# ODROID.net
KiCad netlist of a schematic drawn in Altium Designer
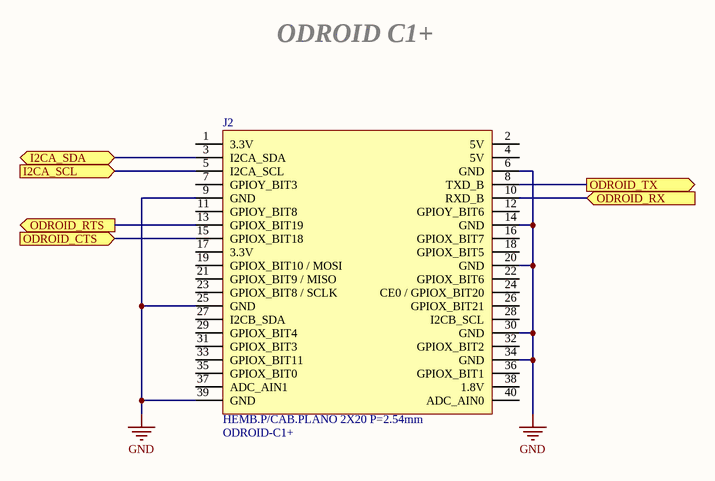
[diagram p0: ODROID.SchDoc]

(export (version "E")
  (design (tool "Eeschema 10.0.6"))
  (components
    (comp (ref "J2")
      (value "HEMB.P/CAB.PLANO 2X20 P=2.54mm")
      (footprint "ODROID_C1+_MOUNTUP")
      (description "Conector para odroid c1+")
      (fields (field (name "ALTIUM_UNNAMED_1") "ODROID-C1+"))
      (libsource (lib "HW_Dron_V2") (part "Odroid_C1+"))
    )
  )
  (nets
    (net (code "1") (name "/I2CA_SCL") (class "Default")
      (node (ref "J2") (pin "5") (pinfunction "I2CA_SCL_5") (pintype "passive"))
    )
    (net (code "2") (name "/I2CA_SDA") (class "Default")
      (node (ref "J2") (pin "3") (pinfunction "I2CA_SDA_3") (pintype "passive"))
    )
    (net (code "3") (name "/ODROID_CTS") (class "Default")
      (node (ref "J2") (pin "15") (pinfunction "GPIOX_BIT18_15") (pintype "passive"))
    )
    (net (code "4") (name "/ODROID_RTS") (class "Default")
      (node (ref "J2") (pin "13") (pinfunction "GPIOX_BIT19_13") (pintype "passive"))
    )
    (net (code "5") (name "/ODROID_RX") (class "Default")
      (node (ref "J2") (pin "10") (pinfunction "RXD_B_10") (pintype "passive"))
    )
    (net (code "6") (name "/ODROID_TX") (class "Default")
      (node (ref "J2") (pin "8") (pinfunction "TXD_B_8") (pintype "passive"))
    )
    (net (code "7") (name "GND") (class "Default")
      (node (ref "J2") (pin "14") (pinfunction "GND_14") (pintype "passive"))
      (node (ref "J2") (pin "20") (pinfunction "GND_20") (pintype "passive"))
      (node (ref "J2") (pin "25") (pinfunction "GND_25") (pintype "passive"))
      (node (ref "J2") (pin "30") (pinfunction "GND_30") (pintype "passive"))
      (node (ref "J2") (pin "34") (pinfunction "GND_34") (pintype "passive"))
      (node (ref "J2") (pin "39") (pinfunction "GND_39") (pintype "passive"))
      (node (ref "J2") (pin "6") (pinfunction "GND_6") (pintype "passive"))
      (node (ref "J2") (pin "9") (pinfunction "GND_9") (pintype "passive"))
    )
    (net (code "8") (name "unconnected-(J2-1.8V-Pad38)") (class "Default")
      (node (ref "J2") (pin "38") (pinfunction "1.8V_38") (pintype "passive"))
    )
    (net (code "9") (name "unconnected-(J2-3.3V-Pad1)") (class "Default")
      (node (ref "J2") (pin "1") (pinfunction "3.3V_1") (pintype "passive"))
    )
    (net (code "10") (name "unconnected-(J2-3.3V-Pad17)") (class "Default")
      (node (ref "J2") (pin "17") (pinfunction "3.3V_17") (pintype "passive"))
    )
    (net (code "11") (name "unconnected-(J2-5V-Pad2)") (class "Default")
      (node (ref "J2") (pin "2") (pinfunction "5V_2") (pintype "passive"))
    )
    (net (code "12") (name "unconnected-(J2-5V-Pad4)") (class "Default")
      (node (ref "J2") (pin "4") (pinfunction "5V_4") (pintype "passive"))
    )
    (net (code "13") (name "unconnected-(J2-ADC_AIN0-Pad40)") (class "Default")
      (node (ref "J2") (pin "40") (pinfunction "ADC_AIN0_40") (pintype "passive"))
    )
    (net (code "14") (name "unconnected-(J2-ADC_AIN1-Pad37)") (class "Default")
      (node (ref "J2") (pin "37") (pinfunction "ADC_AIN1_37") (pintype "passive"))
    )
    (net (code "15") (name "unconnected-(J2-CE0_{slash}_GPIOX_BIT20-Pad24)") (class "Default")
      (node (ref "J2") (pin "24") (pinfunction "CE0_/_GPIOX_BIT20_24") (pintype "passive"))
    )
    (net (code "16") (name "unconnected-(J2-GPIOX_BIT0-Pad35)") (class "Default")
      (node (ref "J2") (pin "35") (pinfunction "GPIOX_BIT0_35") (pintype "passive"))
    )
    (net (code "17") (name "unconnected-(J2-GPIOX_BIT1-Pad36)") (class "Default")
      (node (ref "J2") (pin "36") (pinfunction "GPIOX_BIT1_36") (pintype "passive"))
    )
    (net (code "18") (name "unconnected-(J2-GPIOX_BIT2-Pad32)") (class "Default")
      (node (ref "J2") (pin "32") (pinfunction "GPIOX_BIT2_32") (pintype "passive"))
    )
    (net (code "19") (name "unconnected-(J2-GPIOX_BIT3-Pad31)") (class "Default")
      (node (ref "J2") (pin "31") (pinfunction "GPIOX_BIT3_31") (pintype "passive"))
    )
    (net (code "20") (name "unconnected-(J2-GPIOX_BIT4-Pad29)") (class "Default")
      (node (ref "J2") (pin "29") (pinfunction "GPIOX_BIT4_29") (pintype "passive"))
    )
    (net (code "21") (name "unconnected-(J2-GPIOX_BIT5-Pad18)") (class "Default")
      (node (ref "J2") (pin "18") (pinfunction "GPIOX_BIT5_18") (pintype "passive"))
    )
    (net (code "22") (name "unconnected-(J2-GPIOX_BIT6-Pad22)") (class "Default")
      (node (ref "J2") (pin "22") (pinfunction "GPIOX_BIT6_22") (pintype "passive"))
    )
    (net (code "23") (name "unconnected-(J2-GPIOX_BIT7-Pad16)") (class "Default")
      (node (ref "J2") (pin "16") (pinfunction "GPIOX_BIT7_16") (pintype "passive"))
    )
    (net (code "24") (name "unconnected-(J2-GPIOX_BIT8_{slash}_SCLK-Pad23)") (class "Default")
      (node (ref "J2") (pin "23") (pinfunction "GPIOX_BIT8_/_SCLK_23") (pintype "passive"))
    )
    (net (code "25") (name "unconnected-(J2-GPIOX_BIT9_{slash}_MISO-Pad21)") (class "Default")
      (node (ref "J2") (pin "21") (pinfunction "GPIOX_BIT9_/_MISO_21") (pintype "passive"))
    )
    (net (code "26") (name "unconnected-(J2-GPIOX_BIT10_{slash}_MOSI-Pad19)") (class "Default")
      (node (ref "J2") (pin "19") (pinfunction "GPIOX_BIT10_/_MOSI_19") (pintype "passive"))
    )
    (net (code "27") (name "unconnected-(J2-GPIOX_BIT11-Pad33)") (class "Default")
      (node (ref "J2") (pin "33") (pinfunction "GPIOX_BIT11_33") (pintype "passive"))
    )
    (net (code "28") (name "unconnected-(J2-GPIOX_BIT21-Pad26)") (class "Default")
      (node (ref "J2") (pin "26") (pinfunction "GPIOX_BIT21_26") (pintype "passive"))
    )
    (net (code "29") (name "unconnected-(J2-GPIOY_BIT3-Pad7)") (class "Default")
      (node (ref "J2") (pin "7") (pinfunction "GPIOY_BIT3_7") (pintype "passive"))
    )
    (net (code "30") (name "unconnected-(J2-GPIOY_BIT6-Pad12)") (class "Default")
      (node (ref "J2") (pin "12") (pinfunction "GPIOY_BIT6_12") (pintype "passive"))
    )
    (net (code "31") (name "unconnected-(J2-GPIOY_BIT8-Pad11)") (class "Default")
      (node (ref "J2") (pin "11") (pinfunction "GPIOY_BIT8_11") (pintype "passive"))
    )
    (net (code "32") (name "unconnected-(J2-I2CB_SCL-Pad28)") (class "Default")
      (node (ref "J2") (pin "28") (pinfunction "I2CB_SCL_28") (pintype "passive"))
    )
    (net (code "33") (name "unconnected-(J2-I2CB_SDA-Pad27)") (class "Default")
      (node (ref "J2") (pin "27") (pinfunction "I2CB_SDA_27") (pintype "passive"))
    )
  )
)
